# RefVoltage.net
KiCad netlist of a schematic drawn in EAGLE
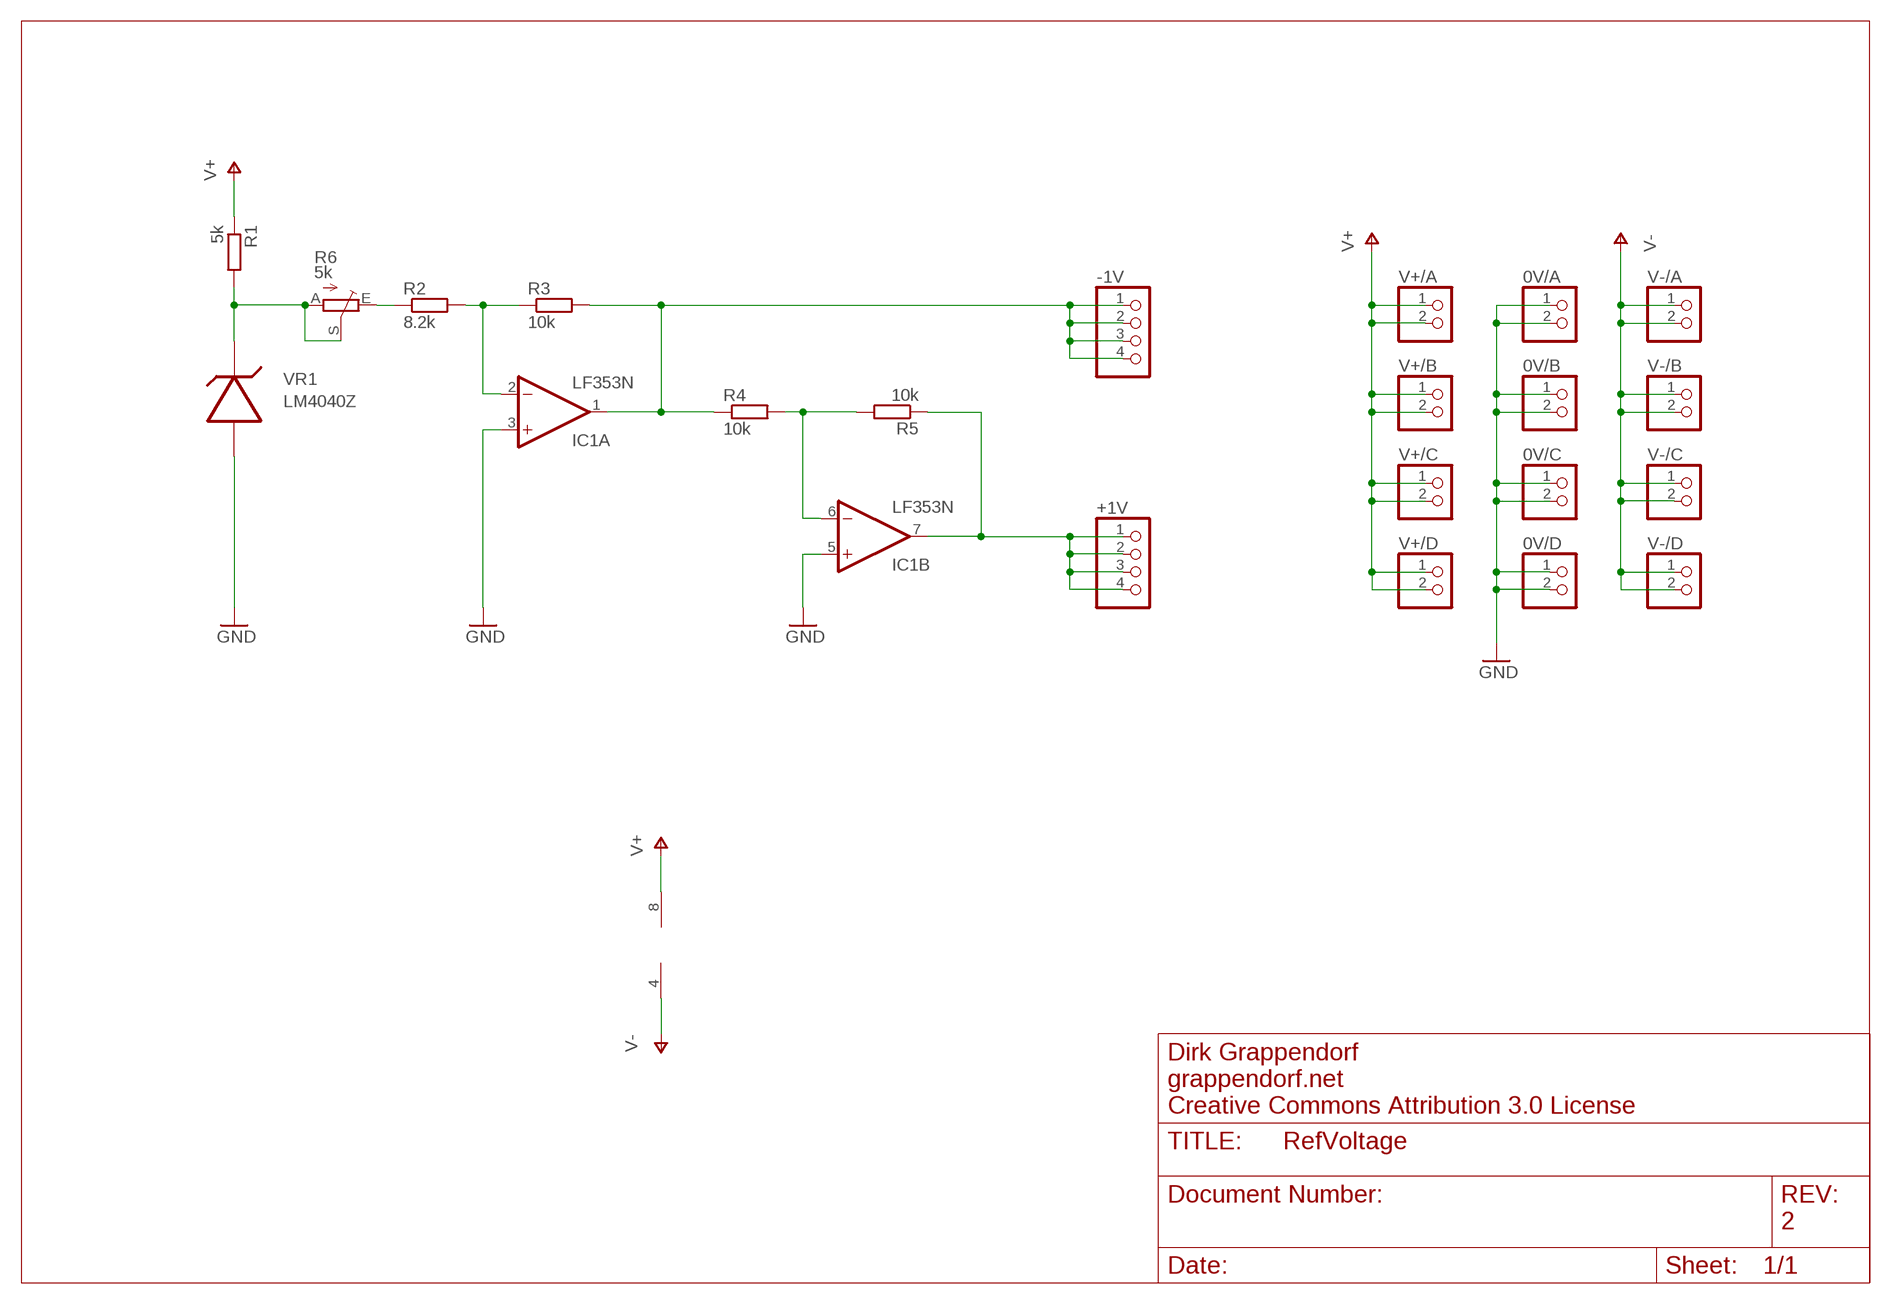
[diagram p0: schematic, sheet 1]

(export (version "E")
  (design (tool "Eeschema 10.0.6"))
  (components
    (comp (ref "+1V")
      (value "PINHD-1X4")
      (footprint "eagle-import:1X04")
      (libsource (lib "eagle-import") (part "PINHD-1X4"))
    )
    (comp (ref "-1V")
      (value "PINHD-1X4")
      (footprint "eagle-import:1X04")
      (libsource (lib "eagle-import") (part "PINHD-1X4"))
    )
    (comp (ref "0V/A")
      (value "PINHD-1X2")
      (footprint "eagle-import:1X02")
      (libsource (lib "eagle-import") (part "PINHD-1X2"))
    )
    (comp (ref "0V/B")
      (value "PINHD-1X2")
      (footprint "eagle-import:1X02")
      (libsource (lib "eagle-import") (part "PINHD-1X2"))
    )
    (comp (ref "0V/C")
      (value "PINHD-1X2")
      (footprint "eagle-import:1X02")
      (libsource (lib "eagle-import") (part "PINHD-1X2"))
    )
    (comp (ref "0V/D")
      (value "PINHD-1X2")
      (footprint "eagle-import:1X02")
      (libsource (lib "eagle-import") (part "PINHD-1X2"))
    )
    (comp (ref "IC1")
      (value "LF353N")
      (footprint "eagle-import:DIL08")
      (libsource (lib "eagle-import") (part "LF353N"))
    )
    (comp (ref "R1")
      (value "5k")
      (footprint "eagle-import:0207_7")
      (libsource (lib "eagle-import") (part "R-EU_0207/7"))
    )
    (comp (ref "R2")
      (value "8.2k")
      (footprint "eagle-import:0207_7")
      (libsource (lib "eagle-import") (part "R-EU_0207/7"))
    )
    (comp (ref "R3")
      (value "10k")
      (footprint "eagle-import:0207_7")
      (libsource (lib "eagle-import") (part "R-EU_0207/7"))
    )
    (comp (ref "R4")
      (value "10k")
      (footprint "eagle-import:0207_7")
      (libsource (lib "eagle-import") (part "R-EU_0207/7"))
    )
    (comp (ref "R5")
      (value "10k")
      (footprint "eagle-import:0207_7")
      (libsource (lib "eagle-import") (part "R-EU_0207/7"))
    )
    (comp (ref "R6")
      (value "5k")
      (footprint "eagle-import:LI10")
      (libsource (lib "eagle-import") (part "TRIM_EU-LI10"))
    )
    (comp (ref "V+/A")
      (value "PINHD-1X2")
      (footprint "eagle-import:1X02")
      (libsource (lib "eagle-import") (part "PINHD-1X2"))
    )
    (comp (ref "V+/B")
      (value "PINHD-1X2")
      (footprint "eagle-import:1X02")
      (libsource (lib "eagle-import") (part "PINHD-1X2"))
    )
    (comp (ref "V+/C")
      (value "PINHD-1X2")
      (footprint "eagle-import:1X02")
      (libsource (lib "eagle-import") (part "PINHD-1X2"))
    )
    (comp (ref "V+/D")
      (value "PINHD-1X2")
      (footprint "eagle-import:1X02")
      (libsource (lib "eagle-import") (part "PINHD-1X2"))
    )
    (comp (ref "V-/A")
      (value "PINHD-1X2")
      (footprint "eagle-import:1X02")
      (libsource (lib "eagle-import") (part "PINHD-1X2"))
    )
    (comp (ref "V-/B")
      (value "PINHD-1X2")
      (footprint "eagle-import:1X02")
      (libsource (lib "eagle-import") (part "PINHD-1X2"))
    )
    (comp (ref "V-/C")
      (value "PINHD-1X2")
      (footprint "eagle-import:1X02")
      (libsource (lib "eagle-import") (part "PINHD-1X2"))
    )
    (comp (ref "V-/D")
      (value "PINHD-1X2")
      (footprint "eagle-import:1X02")
      (libsource (lib "eagle-import") (part "PINHD-1X2"))
    )
    (comp (ref "VR1")
      (value "LM4040Z")
      (footprint "eagle-import:TO92")
      (libsource (lib "eagle-import") (part "LM4040Z"))
    )
  )
  (nets
    (net (code "1") (name "GND") (class "Default")
      (node (ref "0V/A") (pin "1") (pinfunction "1_1") (pintype "passive"))
      (node (ref "0V/A") (pin "2") (pinfunction "2_2") (pintype "passive"))
      (node (ref "0V/B") (pin "1") (pinfunction "1_1") (pintype "passive"))
      (node (ref "0V/B") (pin "2") (pinfunction "2_2") (pintype "passive"))
      (node (ref "0V/C") (pin "1") (pinfunction "1_1") (pintype "passive"))
      (node (ref "0V/C") (pin "2") (pinfunction "2_2") (pintype "passive"))
      (node (ref "0V/D") (pin "1") (pinfunction "1_1") (pintype "passive"))
      (node (ref "0V/D") (pin "2") (pinfunction "2_2") (pintype "passive"))
      (node (ref "IC1") (pin "3") (pinfunction "+IN_3") (pintype "input"))
      (node (ref "IC1") (pin "5") (pinfunction "+IN_5") (pintype "input"))
      (node (ref "VR1") (pin "3") (pinfunction "P$2_3") (pintype "bidirectional"))
    )
    (net (code "2") (name "Net-(IC1A--IN)") (class "Default")
      (node (ref "IC1") (pin "2") (pinfunction "-IN_2") (pintype "input"))
      (node (ref "R2") (pin "2") (pinfunction "2_2") (pintype "passive"))
      (node (ref "R3") (pin "1") (pinfunction "1_1") (pintype "passive"))
    )
    (net (code "3") (name "Net-(IC1A-OUT)") (class "Default")
      (node (ref "-1V") (pin "1") (pinfunction "1_1") (pintype "passive"))
      (node (ref "-1V") (pin "2") (pinfunction "2_2") (pintype "passive"))
      (node (ref "-1V") (pin "3") (pinfunction "3_3") (pintype "passive"))
      (node (ref "-1V") (pin "4") (pinfunction "4_4") (pintype "passive"))
      (node (ref "IC1") (pin "1") (pinfunction "OUT_1") (pintype "output"))
      (node (ref "R3") (pin "2") (pinfunction "2_2") (pintype "passive"))
      (node (ref "R4") (pin "1") (pinfunction "1_1") (pintype "passive"))
    )
    (net (code "4") (name "Net-(IC1B--IN)") (class "Default")
      (node (ref "IC1") (pin "6") (pinfunction "-IN_6") (pintype "input"))
      (node (ref "R4") (pin "2") (pinfunction "2_2") (pintype "passive"))
      (node (ref "R5") (pin "2") (pinfunction "2_2") (pintype "passive"))
    )
    (net (code "5") (name "Net-(IC1B-OUT)") (class "Default")
      (node (ref "+1V") (pin "1") (pinfunction "1_1") (pintype "passive"))
      (node (ref "+1V") (pin "2") (pinfunction "2_2") (pintype "passive"))
      (node (ref "+1V") (pin "3") (pinfunction "3_3") (pintype "passive"))
      (node (ref "+1V") (pin "4") (pinfunction "4_4") (pintype "passive"))
      (node (ref "IC1") (pin "7") (pinfunction "OUT_7") (pintype "output"))
      (node (ref "R5") (pin "1") (pinfunction "1_1") (pintype "passive"))
    )
    (net (code "6") (name "Net-(R2-Pad1)") (class "Default")
      (node (ref "R2") (pin "1") (pinfunction "1_1") (pintype "passive"))
      (node (ref "R6") (pin "E") (pinfunction "E_E") (pintype "passive"))
    )
    (net (code "7") (name "Net-(VR1-P$1)") (class "Default")
      (node (ref "R1") (pin "2") (pinfunction "2_2") (pintype "passive"))
      (node (ref "R6") (pin "A") (pinfunction "A_A") (pintype "passive"))
      (node (ref "R6") (pin "S") (pinfunction "S_S") (pintype "passive"))
      (node (ref "VR1") (pin "2") (pinfunction "P$1_2") (pintype "bidirectional"))
    )
    (net (code "8") (name "V+") (class "Default")
      (node (ref "IC1") (pin "8") (pinfunction "V+_8") (pintype "power_in"))
      (node (ref "R1") (pin "1") (pinfunction "1_1") (pintype "passive"))
      (node (ref "V+/A") (pin "1") (pinfunction "1_1") (pintype "passive"))
      (node (ref "V+/A") (pin "2") (pinfunction "2_2") (pintype "passive"))
      (node (ref "V+/B") (pin "1") (pinfunction "1_1") (pintype "passive"))
      (node (ref "V+/B") (pin "2") (pinfunction "2_2") (pintype "passive"))
      (node (ref "V+/C") (pin "1") (pinfunction "1_1") (pintype "passive"))
      (node (ref "V+/C") (pin "2") (pinfunction "2_2") (pintype "passive"))
      (node (ref "V+/D") (pin "1") (pinfunction "1_1") (pintype "passive"))
      (node (ref "V+/D") (pin "2") (pinfunction "2_2") (pintype "passive"))
    )
    (net (code "9") (name "V-") (class "Default")
      (node (ref "IC1") (pin "4") (pinfunction "V-_4") (pintype "power_in"))
      (node (ref "V-/A") (pin "1") (pinfunction "1_1") (pintype "passive"))
      (node (ref "V-/A") (pin "2") (pinfunction "2_2") (pintype "passive"))
      (node (ref "V-/B") (pin "1") (pinfunction "1_1") (pintype "passive"))
      (node (ref "V-/B") (pin "2") (pinfunction "2_2") (pintype "passive"))
      (node (ref "V-/C") (pin "1") (pinfunction "1_1") (pintype "passive"))
      (node (ref "V-/C") (pin "2") (pinfunction "2_2") (pintype "passive"))
      (node (ref "V-/D") (pin "1") (pinfunction "1_1") (pintype "passive"))
      (node (ref "V-/D") (pin "2") (pinfunction "2_2") (pintype "passive"))
    )
  )
)
